# LPCB235_-_MAGNETICS.net
KiCad netlist of a schematic drawn in Altium Designer
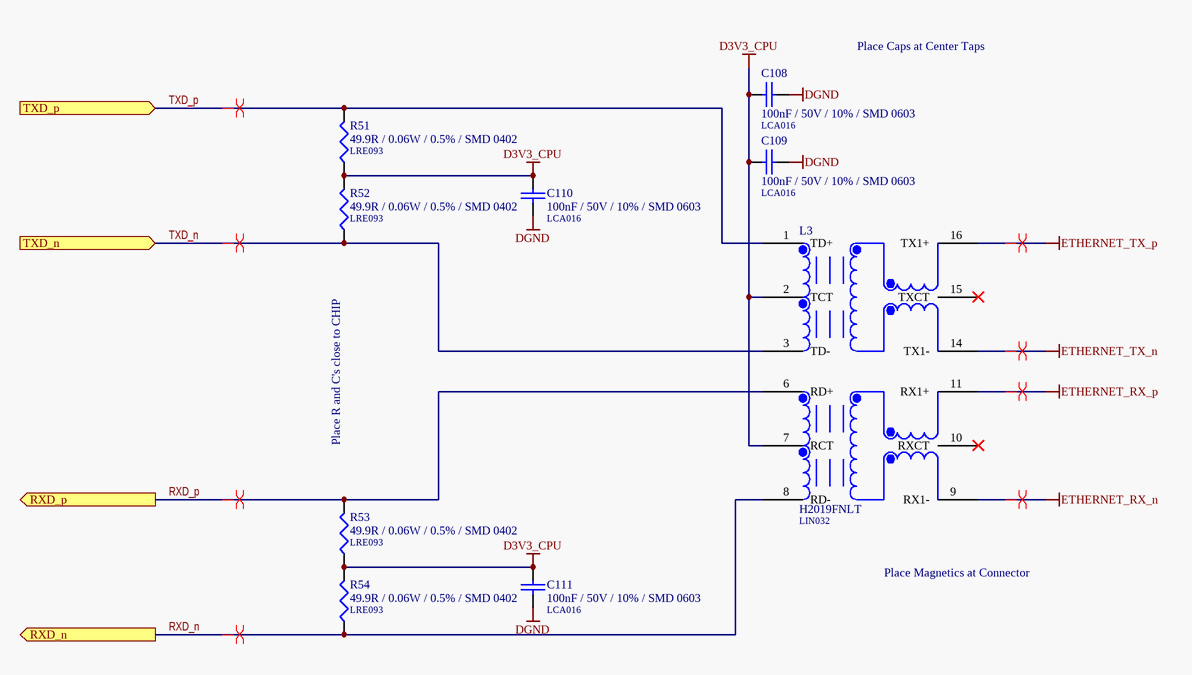
[diagram p0: LPCB235 - MAGNETICS.SchDoc]

(export (version "E")
  (design (tool "Eeschema 10.0.6"))
  (components
    (comp (ref "C108")
      (value "100nF / 50V / 10% / SMD 0603")
      (footprint "LFP011__CC1608-0603-IPC7351_B")
      (description "Capacitor, Ceramic Chip, 100nF (0.1uF), 50V, 5%, SMD 0603 [LCA016]")
      (fields (field (name "LDL_NUMBER") "LCA016"))
      (libsource (lib "LDL_Capacitors") (part "100nF / 50V / 10% / SMD 0603"))
    )
    (comp (ref "C109")
      (value "100nF / 50V / 10% / SMD 0603")
      (footprint "LFP011__CC1608-0603-IPC7351_B")
      (description "Capacitor, Ceramic Chip, 100nF (0.1uF), 50V, 5%, SMD 0603 [LCA016]")
      (fields (field (name "LDL_NUMBER") "LCA016"))
      (libsource (lib "LDL_Capacitors") (part "100nF / 50V / 10% / SMD 0603"))
    )
    (comp (ref "C110")
      (value "100nF / 50V / 10% / SMD 0603")
      (footprint "LFP011__CC1608-0603-IPC7351_B")
      (description "Capacitor, Ceramic Chip, 100nF (0.1uF), 50V, 5%, SMD 0603 [LCA016]")
      (fields (field (name "LDL_NUMBER") "LCA016"))
      (libsource (lib "LDL_Capacitors") (part "100nF / 50V / 10% / SMD 0603"))
    )
    (comp (ref "C111")
      (value "100nF / 50V / 10% / SMD 0603")
      (footprint "LFP011__CC1608-0603-IPC7351_B")
      (description "Capacitor, Ceramic Chip, 100nF (0.1uF), 50V, 5%, SMD 0603 [LCA016]")
      (fields (field (name "LDL_NUMBER") "LCA016"))
      (libsource (lib "LDL_Capacitors") (part "100nF / 50V / 10% / SMD 0603"))
    )
    (comp (ref "L3")
      (value "H2019FNLT")
      (footprint "LFP076__H2019NL")
      (description "Transformer, Signal Transformers, SMD [LIN032]")
      (fields (field (name "LDL_NUMBER") "LIN032"))
      (libsource (lib "LDL_Inductors") (part "H2019FNLT"))
    )
    (comp (ref "R51")
      (value "49.9R / 0.06W / 0.5% / SMD 0402")
      (footprint "LFP030__CR1005-0402-IPC7351")
      (description "Resistor, Ceramic Chip, 49.9R, 0.0625W, 0.5%, SMD 0402 [LRE093]")
      (fields (field (name "LDL_NUMBER") "LRE093"))
      (libsource (lib "LDL_Resistors") (part "49.9R / 0.06W / 0.5% / SMD 0402"))
    )
    (comp (ref "R52")
      (value "49.9R / 0.06W / 0.5% / SMD 0402")
      (footprint "LFP030__CR1005-0402-IPC7351")
      (description "Resistor, Ceramic Chip, 49.9R, 0.0625W, 0.5%, SMD 0402 [LRE093]")
      (fields (field (name "LDL_NUMBER") "LRE093"))
      (libsource (lib "LDL_Resistors") (part "49.9R / 0.06W / 0.5% / SMD 0402"))
    )
    (comp (ref "R53")
      (value "49.9R / 0.06W / 0.5% / SMD 0402")
      (footprint "LFP030__CR1005-0402-IPC7351")
      (description "Resistor, Ceramic Chip, 49.9R, 0.0625W, 0.5%, SMD 0402 [LRE093]")
      (fields (field (name "LDL_NUMBER") "LRE093"))
      (libsource (lib "LDL_Resistors") (part "49.9R / 0.06W / 0.5% / SMD 0402"))
    )
    (comp (ref "R54")
      (value "49.9R / 0.06W / 0.5% / SMD 0402")
      (footprint "LFP030__CR1005-0402-IPC7351")
      (description "Resistor, Ceramic Chip, 49.9R, 0.0625W, 0.5%, SMD 0402 [LRE093]")
      (fields (field (name "LDL_NUMBER") "LRE093"))
      (libsource (lib "LDL_Resistors") (part "49.9R / 0.06W / 0.5% / SMD 0402"))
    )
  )
  (nets
    (net (code "1") (name "/RXD_n") (class "Default")
      (node (ref "L3") (pin "8") (pinfunction "RD-_8") (pintype "passive"))
      (node (ref "R54") (pin "1") (pintype "passive"))
    )
    (net (code "2") (name "/RXD_p") (class "Default")
      (node (ref "L3") (pin "6") (pinfunction "RD+_6") (pintype "passive"))
      (node (ref "R53") (pin "2") (pintype "passive"))
    )
    (net (code "3") (name "/TXD_n") (class "Default")
      (node (ref "L3") (pin "3") (pinfunction "TD-_3") (pintype "passive"))
      (node (ref "R52") (pin "1") (pintype "passive"))
    )
    (net (code "4") (name "/TXD_p") (class "Default")
      (node (ref "L3") (pin "1") (pinfunction "TD+_1") (pintype "passive"))
      (node (ref "R51") (pin "2") (pintype "passive"))
    )
    (net (code "5") (name "D3V3_CPU") (class "Default")
      (node (ref "C108") (pin "1") (pintype "passive"))
      (node (ref "C109") (pin "1") (pintype "passive"))
      (node (ref "C110") (pin "1") (pintype "passive"))
      (node (ref "C111") (pin "1") (pintype "passive"))
      (node (ref "L3") (pin "2") (pinfunction "TCT_2") (pintype "passive"))
      (node (ref "L3") (pin "7") (pinfunction "RCT_7") (pintype "passive"))
      (node (ref "R51") (pin "1") (pintype "passive"))
      (node (ref "R52") (pin "2") (pintype "passive"))
      (node (ref "R53") (pin "1") (pintype "passive"))
      (node (ref "R54") (pin "2") (pintype "passive"))
    )
    (net (code "6") (name "DGND") (class "Default")
      (node (ref "C108") (pin "2") (pintype "passive"))
      (node (ref "C109") (pin "2") (pintype "passive"))
      (node (ref "C110") (pin "2") (pintype "passive"))
      (node (ref "C111") (pin "2") (pintype "passive"))
    )
    (net (code "7") (name "ETHERNET_RX_n") (class "Default")
      (node (ref "L3") (pin "9") (pinfunction "RX1-_9") (pintype "passive"))
    )
    (net (code "8") (name "ETHERNET_RX_p") (class "Default")
      (node (ref "L3") (pin "11") (pinfunction "RX1+_11") (pintype "passive"))
    )
    (net (code "9") (name "ETHERNET_TX_n") (class "Default")
      (node (ref "L3") (pin "14") (pinfunction "TX1-_14") (pintype "passive"))
    )
    (net (code "10") (name "ETHERNET_TX_p") (class "Default")
      (node (ref "L3") (pin "16") (pinfunction "TX1+_16") (pintype "passive"))
    )
    (net (code "11") (name "unconnected-(L3-RXCT-Pad10)") (class "Default")
      (node (ref "L3") (pin "10") (pinfunction "RXCT_10") (pintype "passive+no_connect"))
    )
    (net (code "12") (name "unconnected-(L3-TXCT-Pad15)") (class "Default")
      (node (ref "L3") (pin "15") (pinfunction "TXCT_15") (pintype "passive+no_connect"))
    )
  )
)
